# design.net
KiCad netlist of a schematic drawn in Altium Designer
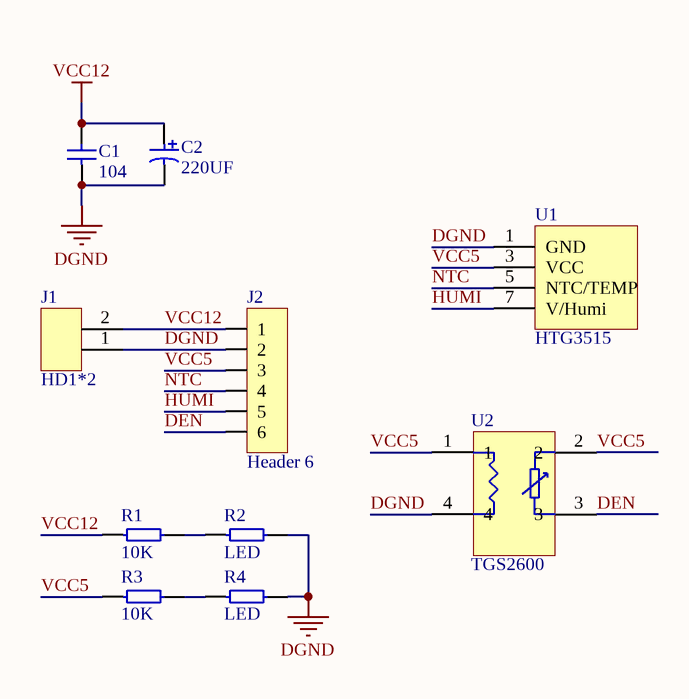
[diagram p0: 浓度探头.SchDoc]

(export (version "E")
  (design (tool "Eeschema 10.0.6"))
  (components
    (comp (ref "C1") (value "104") (footprint "0805C") (libsource (lib "basic") (part "CAP")))
    (comp (ref "C2") (value "220UF") (footprint "RB 2.5/6.3") (libsource (lib "basic") (part "CAP-POL2")))
    (comp (ref "J1") (value "HD1*2") (footprint "XH2.54-2P") (libsource (lib "接插件") (part "HD1*2")))
    (comp (ref "J2")
      (value "Header 6")
      (footprint "KF128 6-2.54")
      (libsource (lib "Connectors") (part "Header 6"))
    )
    (comp (ref "R1") (value "10K") (footprint "0805") (libsource (lib "基本元件") (part "Res")))
    (comp (ref "R2") (value "LED") (footprint "0805") (libsource (lib "基本元件") (part "Res")))
    (comp (ref "R3") (value "10K") (footprint "0805") (libsource (lib "基本元件") (part "Res")))
    (comp (ref "R4") (value "LED") (footprint "0805") (libsource (lib "基本元件") (part "Res")))
    (comp (ref "U1") (value "HTG3515") (footprint "HD2*4-2.0") (libsource (lib "常用芯片") (part "HTG3515")))
    (comp (ref "U2") (value "TGS2600") (footprint "TGS2600") (libsource (lib "常用芯片") (part "TGS2600")))
  )
  (nets
    (net (code "1") (name "/DEN") (class "Default")
      (node (ref "J2") (pin "6") (pinfunction "6_6") (pintype "passive"))
      (node (ref "U2") (pin "3") (pinfunction "3_3") (pintype "passive"))
    )
    (net (code "2") (name "/HUMI") (class "Default")
      (node (ref "J2") (pin "5") (pinfunction "5_5") (pintype "passive"))
      (node (ref "U1") (pin "7") (pinfunction "V/Humi_7") (pintype "passive"))
    )
    (net (code "3") (name "/NTC") (class "Default")
      (node (ref "J2") (pin "4") (pinfunction "4_4") (pintype "passive"))
      (node (ref "U1") (pin "5") (pinfunction "NTC/TEMP_5") (pintype "passive"))
    )
    (net (code "4") (name "/VCC5") (class "Default")
      (node (ref "J2") (pin "3") (pinfunction "3_3") (pintype "passive"))
      (node (ref "R3") (pin "1") (pinfunction "1_1") (pintype "passive"))
      (node (ref "U1") (pin "3") (pinfunction "VCC_3") (pintype "passive"))
      (node (ref "U2") (pin "1") (pinfunction "1_1") (pintype "passive"))
      (node (ref "U2") (pin "2") (pinfunction "2_2") (pintype "passive"))
    )
    (net (code "5") (name "DGND") (class "Default")
      (node (ref "C1") (pin "1") (pinfunction "1_1") (pintype "passive"))
      (node (ref "C2") (pin "1") (pinfunction "1_1") (pintype "passive"))
      (node (ref "J1") (pin "1") (pinfunction "1_1") (pintype "passive"))
      (node (ref "J2") (pin "2") (pinfunction "2_2") (pintype "passive"))
      (node (ref "R2") (pin "2") (pinfunction "2_2") (pintype "passive"))
      (node (ref "R4") (pin "2") (pinfunction "2_2") (pintype "passive"))
      (node (ref "U1") (pin "1") (pinfunction "GND_1") (pintype "passive"))
      (node (ref "U2") (pin "4") (pinfunction "4_4") (pintype "passive"))
    )
    (net (code "6") (name "Net-(R1-Pad2)") (class "Default")
      (node (ref "R1") (pin "2") (pinfunction "2_2") (pintype "passive"))
      (node (ref "R2") (pin "1") (pinfunction "1_1") (pintype "passive"))
    )
    (net (code "7") (name "Net-(R3-Pad2)") (class "Default")
      (node (ref "R3") (pin "2") (pinfunction "2_2") (pintype "passive"))
      (node (ref "R4") (pin "1") (pinfunction "1_1") (pintype "passive"))
    )
    (net (code "8") (name "VCC12") (class "Default")
      (node (ref "C1") (pin "2") (pinfunction "2_2") (pintype "passive"))
      (node (ref "C2") (pin "2") (pinfunction "2_2") (pintype "passive"))
      (node (ref "J1") (pin "2") (pinfunction "2_2") (pintype "passive"))
      (node (ref "J2") (pin "1") (pinfunction "1_1") (pintype "passive"))
      (node (ref "R1") (pin "1") (pinfunction "1_1") (pintype "passive"))
    )
  )
)
